# Tray2_Comms_SwC.net
KiCad netlist of a schematic drawn in Altium Designer
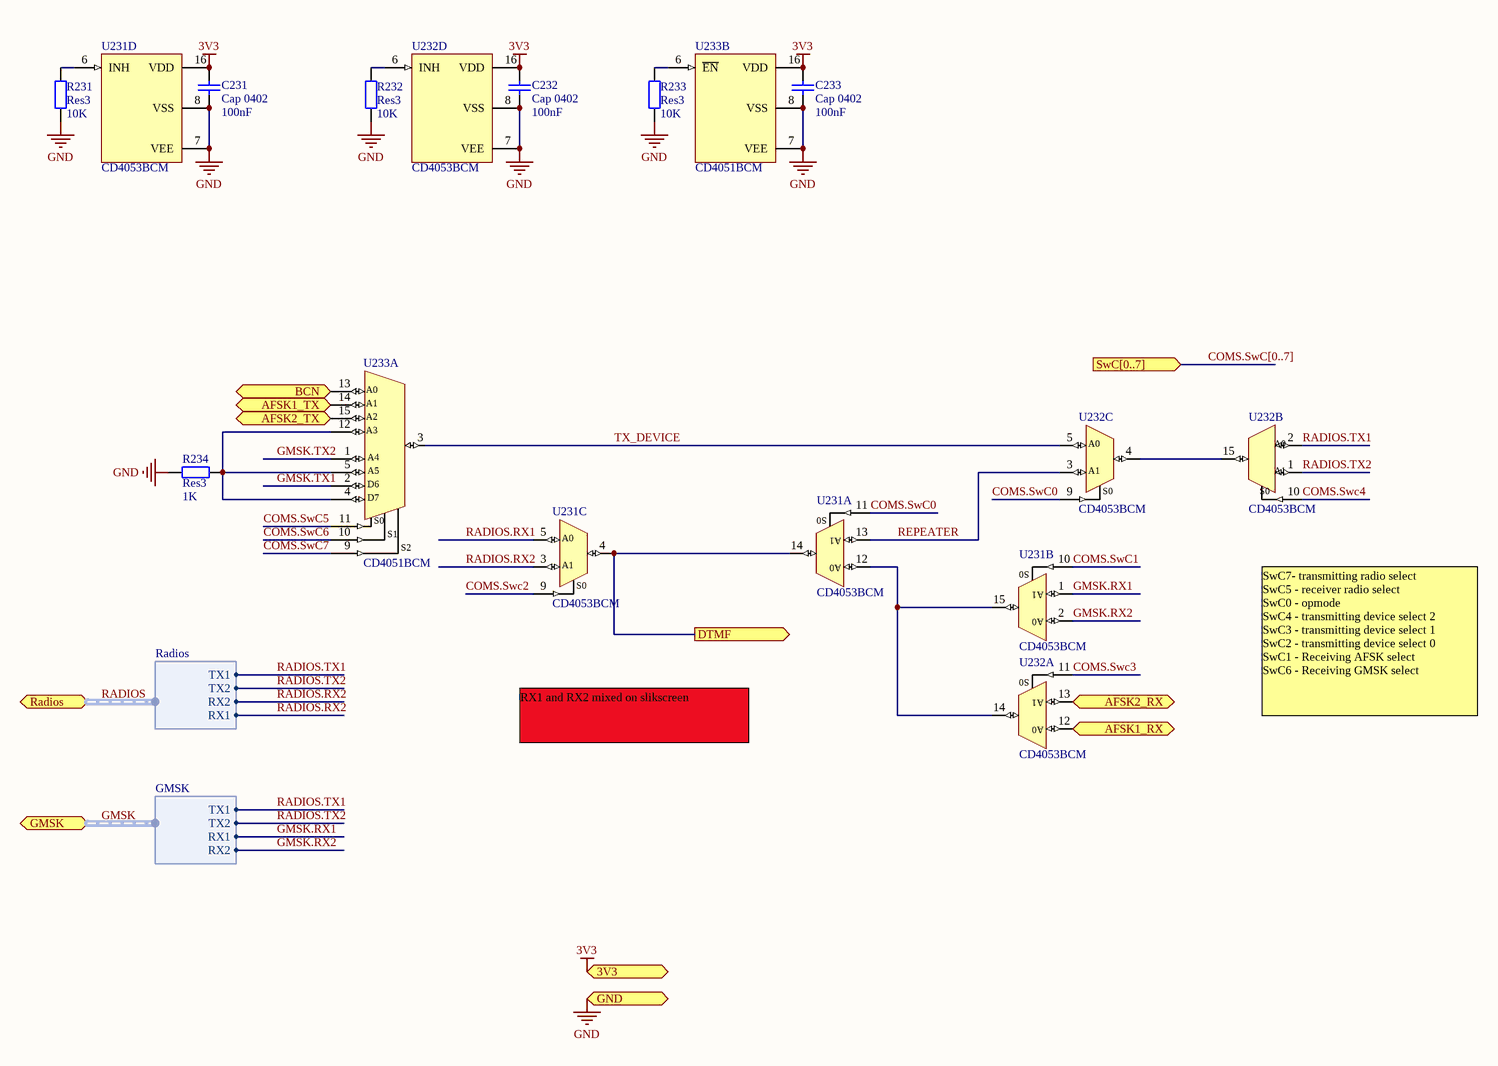
[diagram p0: Tray2_Comms_SwC.SchDoc]

(export (version "E")
  (design (tool "Eeschema 10.0.6"))
  (components
    (comp (ref "C231")
      (value "Cap 0402")
      (footprint "CAPC1005X06L")
      (description "Capacitor")
      (fields (field (name "ALTIUM_VALUE") "100nF") (field (name "PUBLISHER") "Altium Limited"))
      (libsource (lib "CSC") (part "Cap 0402"))
    )
    (comp (ref "C232")
      (value "Cap 0402")
      (footprint "CAPC1005X06L")
      (description "Capacitor")
      (fields (field (name "ALTIUM_VALUE") "100nF") (field (name "PUBLISHER") "Altium Limited"))
      (libsource (lib "CSC") (part "Cap 0402"))
    )
    (comp (ref "C233")
      (value "Cap 0402")
      (footprint "CAPC1005X06L")
      (description "Capacitor")
      (fields (field (name "ALTIUM_VALUE") "100nF") (field (name "PUBLISHER") "Altium Limited"))
      (libsource (lib "CSC") (part "Cap 0402"))
    )
    (comp (ref "R231")
      (value "Res3")
      (footprint "RESC1005X06L")
      (description "Resistor")
      (fields (field (name "ALTIUM_VALUE") "10K") (field (name "PUBLISHER") "Altium Limited"))
      (libsource (lib "CSC") (part "Res3"))
    )
    (comp (ref "R232")
      (value "Res3")
      (footprint "RESC1005X06L")
      (description "Resistor")
      (fields (field (name "ALTIUM_VALUE") "10K") (field (name "PUBLISHER") "Altium Limited"))
      (libsource (lib "CSC") (part "Res3"))
    )
    (comp (ref "R233")
      (value "Res3")
      (footprint "RESC1005X06L")
      (description "Resistor")
      (fields (field (name "ALTIUM_VALUE") "10K") (field (name "PUBLISHER") "Altium Limited"))
      (libsource (lib "CSC") (part "Res3"))
    )
    (comp (ref "R234")
      (value "Res3")
      (footprint "RESC1005X06L")
      (description "Resistor")
      (fields (field (name "ALTIUM_VALUE") "1K") (field (name "PUBLISHER") "Altium Limited"))
      (libsource (lib "") (part "Res3_1"))
    )
    (comp (ref "U231")
      (value "CD4053BCM")
      (footprint "Comms Board Small Footprints:TSSOP16")
      (description "Triple 2-Channnel Analog Multiplexer/Demutiplexer")
      (libsource (lib "Comms Board Small Footprints") (part "CD4053BCM"))
    )
    (comp (ref "U232")
      (value "CD4053BCM")
      (footprint "Comms Board Small Footprints:TSSOP16")
      (description "Triple 2-Channnel Analog Multiplexer/Demutiplexer")
      (libsource (lib "Comms Board Small Footprints") (part "CD4053BCM"))
    )
    (comp (ref "U233")
      (value "CD4051BCM")
      (footprint "Comms Board Small Footprints:TSSOP16")
      (description "8-Channel Analog Multiplexer/Demultiplexer")
      (libsource (lib "") (part "CD4051BCM_1"))
    )
  )
  (nets
    (net (code "6") (name "/AFSK1_RX") (class "Default")
      (node (ref "U232") (pin "12") (pinfunction "A0_12") (pintype "bidirectional"))
    )
    (net (code "7") (name "/AFSK1_TX") (class "Default")
      (node (ref "U233") (pin "14") (pinfunction "A1_14") (pintype "bidirectional"))
    )
    (net (code "8") (name "/AFSK2_RX") (class "Default")
      (node (ref "U232") (pin "13") (pinfunction "A1_13") (pintype "bidirectional"))
    )
    (net (code "9") (name "/AFSK2_TX") (class "Default")
      (node (ref "U233") (pin "15") (pinfunction "A2_15") (pintype "bidirectional"))
    )
    (net (code "10") (name "/BCN") (class "Default")
      (node (ref "U233") (pin "13") (pinfunction "A0_13") (pintype "bidirectional"))
    )
    (net (code "11") (name "/COMS.SwC0") (class "Default")
      (node (ref "U231") (pin "11") (pinfunction "A_11") (pintype "input"))
      (node (ref "U232") (pin "9") (pinfunction "C_9") (pintype "input"))
    )
    (net (code "12") (name "/COMS.SwC1") (class "Default")
      (node (ref "U231") (pin "10") (pinfunction "B_10") (pintype "input"))
    )
    (net (code "13") (name "/COMS.SwC5") (class "Default")
      (node (ref "U233") (pin "11") (pinfunction "S0_11") (pintype "input"))
    )
    (net (code "14") (name "/COMS.SwC6") (class "Default")
      (node (ref "U233") (pin "10") (pinfunction "S1_10") (pintype "input"))
    )
    (net (code "15") (name "/COMS.SwC7") (class "Default")
      (node (ref "U233") (pin "9") (pinfunction "S2_9") (pintype "input"))
    )
    (net (code "17") (name "/COMS.Swc2") (class "Default")
      (node (ref "U231") (pin "9") (pinfunction "C_9") (pintype "input"))
    )
    (net (code "18") (name "/COMS.Swc3") (class "Default")
      (node (ref "U232") (pin "11") (pinfunction "A_11") (pintype "input"))
    )
    (net (code "19") (name "/COMS.Swc4") (class "Default")
      (node (ref "U232") (pin "10") (pinfunction "B_10") (pintype "input"))
    )
    (net (code "20") (name "/DTMF") (class "Default")
      (node (ref "U231") (pin "14") (pinfunction "A_out_14") (pintype "bidirectional"))
      (node (ref "U231") (pin "4") (pinfunction "c_out_4") (pintype "bidirectional"))
    )
    (net (code "21") (name "/GMSK.RX1") (class "Default")
      (node (ref "U231") (pin "1") (pinfunction "by_1") (pintype "bidirectional"))
    )
    (net (code "22") (name "/GMSK.RX2") (class "Default")
      (node (ref "U231") (pin "2") (pinfunction "bx_2") (pintype "bidirectional"))
    )
    (net (code "23") (name "/GMSK.TX1") (class "Default")
      (node (ref "U233") (pin "2") (pinfunction "A6_2") (pintype "bidirectional"))
    )
    (net (code "24") (name "/GMSK.TX2") (class "Default")
      (node (ref "U233") (pin "1") (pinfunction "A4_1") (pintype "bidirectional"))
    )
    (net (code "26") (name "/RADIOS.RX1") (class "Default")
      (node (ref "U231") (pin "5") (pinfunction "cx_5") (pintype "bidirectional"))
    )
    (net (code "27") (name "/RADIOS.RX2") (class "Default")
      (node (ref "U231") (pin "3") (pinfunction "cy_3") (pintype "bidirectional"))
    )
    (net (code "28") (name "/RADIOS.TX1") (class "Default")
      (node (ref "U232") (pin "2") (pinfunction "bx_2") (pintype "bidirectional"))
    )
    (net (code "29") (name "/RADIOS.TX2") (class "Default")
      (node (ref "U232") (pin "1") (pinfunction "by_1") (pintype "bidirectional"))
    )
    (net (code "31") (name "/REPEATER") (class "Default")
      (node (ref "U231") (pin "13") (pinfunction "A1_13") (pintype "bidirectional"))
      (node (ref "U232") (pin "3") (pinfunction "cy_3") (pintype "bidirectional"))
    )
    (net (code "32") (name "/TX_DEVICE") (class "Default")
      (node (ref "U232") (pin "5") (pinfunction "cx_5") (pintype "bidirectional"))
      (node (ref "U233") (pin "3") (pinfunction "O_3") (pintype "bidirectional"))
    )
    (net (code "33") (name "3V3") (class "Default")
      (node (ref "C231") (pin "2") (pinfunction "2_2") (pintype "passive"))
      (node (ref "C232") (pin "2") (pinfunction "2_2") (pintype "passive"))
      (node (ref "C233") (pin "2") (pinfunction "2_2") (pintype "passive"))
      (node (ref "U231") (pin "16") (pinfunction "VDD_16") (pintype "power_in"))
      (node (ref "U232") (pin "16") (pinfunction "VDD_16") (pintype "power_in"))
      (node (ref "U233") (pin "16") (pinfunction "VDD_16") (pintype "power_in"))
    )
    (net (code "34") (name "GND") (class "Default")
      (node (ref "C231") (pin "1") (pinfunction "1_1") (pintype "passive"))
      (node (ref "C232") (pin "1") (pinfunction "1_1") (pintype "passive"))
      (node (ref "C233") (pin "1") (pinfunction "1_1") (pintype "passive"))
      (node (ref "R231") (pin "2") (pinfunction "2_2") (pintype "passive"))
      (node (ref "R232") (pin "2") (pinfunction "2_2") (pintype "passive"))
      (node (ref "R233") (pin "2") (pinfunction "2_2") (pintype "passive"))
      (node (ref "R234") (pin "1") (pinfunction "1_1") (pintype "passive"))
      (node (ref "U231") (pin "7") (pinfunction "VEE_7") (pintype "power_in"))
      (node (ref "U231") (pin "8") (pinfunction "VSS_8") (pintype "power_in"))
      (node (ref "U232") (pin "7") (pinfunction "VEE_7") (pintype "power_in"))
      (node (ref "U232") (pin "8") (pinfunction "VSS_8") (pintype "power_in"))
      (node (ref "U233") (pin "7") (pinfunction "VEE_7") (pintype "power_in"))
      (node (ref "U233") (pin "8") (pinfunction "VSS_8") (pintype "power_in"))
    )
    (net (code "35") (name "Net-(U231A-A0)") (class "Default")
      (node (ref "U231") (pin "12") (pinfunction "A0_12") (pintype "bidirectional"))
      (node (ref "U231") (pin "15") (pinfunction "b_out_15") (pintype "bidirectional"))
      (node (ref "U232") (pin "14") (pinfunction "A_out_14") (pintype "bidirectional"))
    )
    (net (code "36") (name "Net-(U231D-INH)") (class "Default")
      (node (ref "R231") (pin "1") (pinfunction "1_1") (pintype "passive"))
      (node (ref "U231") (pin "6") (pinfunction "INH_6") (pintype "input"))
    )
    (net (code "37") (name "Net-(U232B-b_out)") (class "Default")
      (node (ref "U232") (pin "15") (pinfunction "b_out_15") (pintype "bidirectional"))
      (node (ref "U232") (pin "4") (pinfunction "c_out_4") (pintype "bidirectional"))
    )
    (net (code "38") (name "Net-(U232D-INH)") (class "Default")
      (node (ref "R232") (pin "1") (pinfunction "1_1") (pintype "passive"))
      (node (ref "U232") (pin "6") (pinfunction "INH_6") (pintype "input"))
    )
    (net (code "39") (name "Net-(U233A-A3)") (class "Default")
      (node (ref "R234") (pin "2") (pinfunction "2_2") (pintype "passive"))
      (node (ref "U233") (pin "12") (pinfunction "A3_12") (pintype "bidirectional"))
      (node (ref "U233") (pin "4") (pinfunction "A7_4") (pintype "bidirectional"))
      (node (ref "U233") (pin "5") (pinfunction "A5_5") (pintype "bidirectional"))
    )
    (net (code "40") (name "Net-(U233B-~{EN})") (class "Default")
      (node (ref "R233") (pin "1") (pinfunction "1_1") (pintype "passive"))
      (node (ref "U233") (pin "6") (pinfunction "~{EN}_6") (pintype "input"))
    )
  )
)
